# 03_USB_TO_UART.net
KiCad netlist of a schematic drawn in Altium Designer
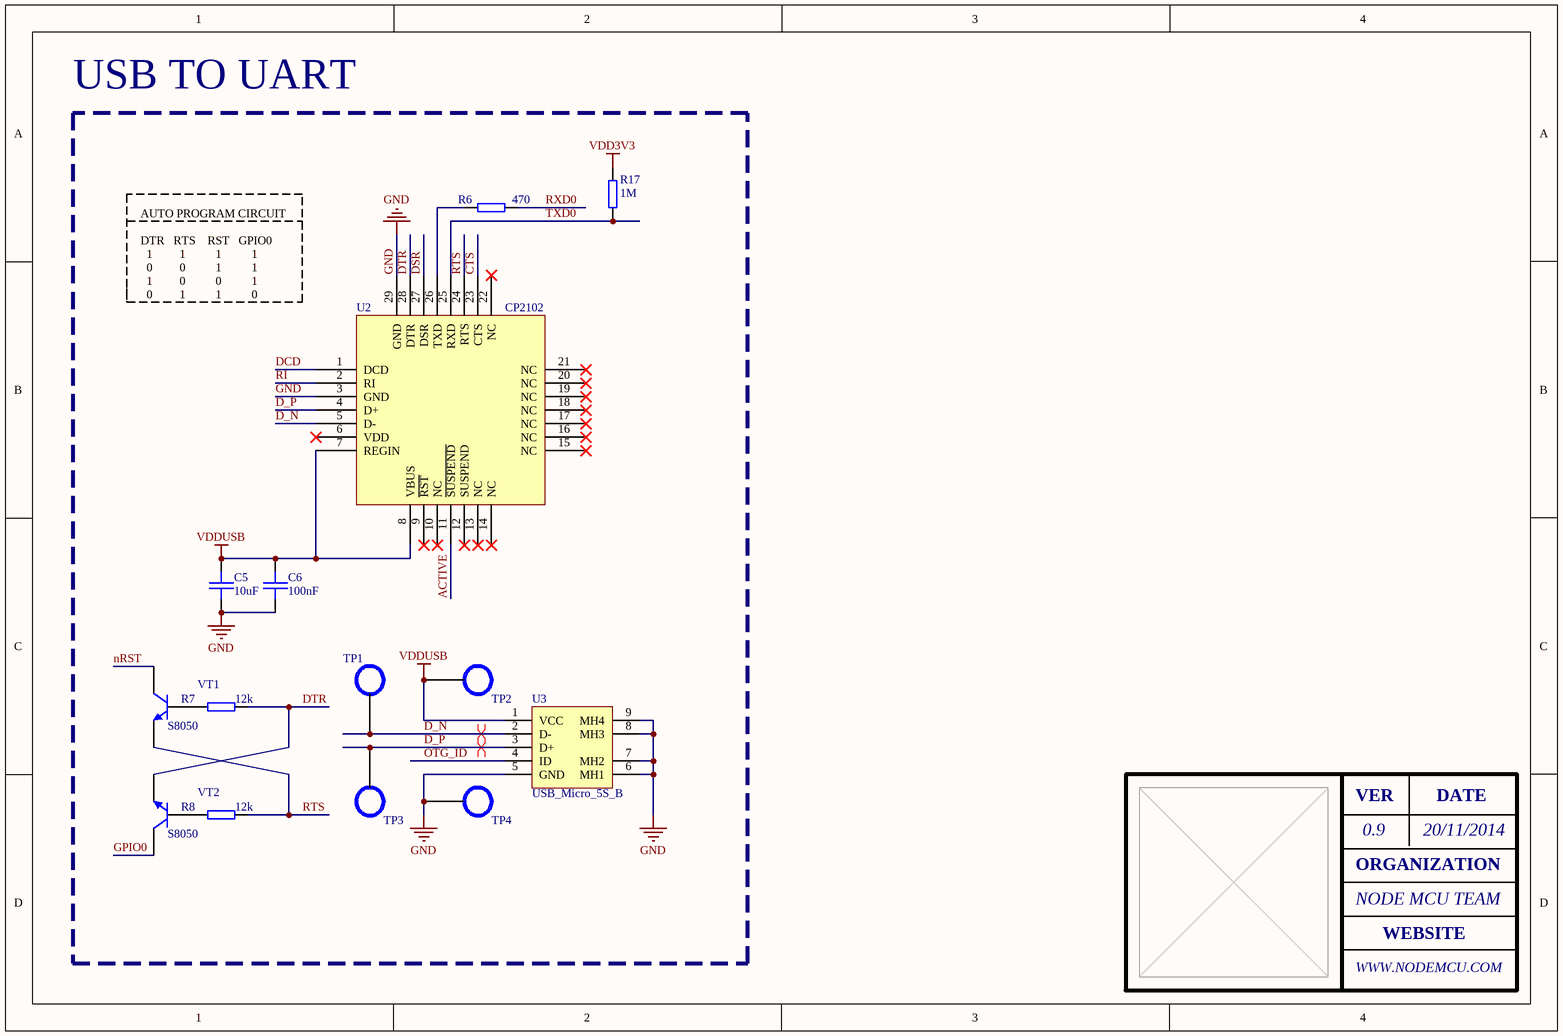
[diagram p0: 03_USB_TO_UART.SchDoc]

(export (version "E")
  (design (tool "Eeschema 10.0.6"))
  (components
    (comp (ref "C5")
      (value "10uF")
      (footprint "SMT_C_0402")
      (description "Surface mount capacitor 0402")
      (libsource (lib "Vowstar_Basic_Device") (part "SMT_C_0402"))
    )
    (comp (ref "C6")
      (value "100nF")
      (footprint "SMT_C_0402")
      (description "Surface mount capacitor 0402")
      (libsource (lib "Vowstar_Basic_Device") (part "SMT_C_0402"))
    )
    (comp (ref "R6")
      (value "470")
      (footprint "SMT_R_0402")
      (description "Surface mount resistor 0402")
      (libsource (lib "Vowstar_Basic_Device") (part "SMT_R_0402"))
    )
    (comp (ref "R7")
      (value "12k")
      (footprint "SMT_R_0402")
      (description "Surface mount resistor 0402")
      (libsource (lib "Vowstar_Basic_Device") (part "SMT_R_0402"))
    )
    (comp (ref "R8")
      (value "12k")
      (footprint "SMT_R_0402")
      (description "Surface mount resistor 0402")
      (libsource (lib "Vowstar_Basic_Device") (part "SMT_R_0402"))
    )
    (comp (ref "R17")
      (value "1M")
      (footprint "SMT_R_0402")
      (description "Surface mount resistor 0402")
      (libsource (lib "Vowstar_Basic_Device") (part "SMT_R_0402"))
    )
    (comp (ref "TP1")
      (value "TEST_POINT")
      (footprint "TEST_POINT")
      (description "Test point")
      (libsource (lib "koruza-compute-module-board") (part "TEST_POINT"))
    )
    (comp (ref "TP2")
      (value "TEST_POINT")
      (footprint "TEST_POINT")
      (description "Test point")
      (libsource (lib "koruza-compute-module-board") (part "TEST_POINT"))
    )
    (comp (ref "TP3")
      (value "TEST_POINT")
      (footprint "TEST_POINT")
      (description "Test point")
      (libsource (lib "koruza-compute-module-board") (part "TEST_POINT"))
    )
    (comp (ref "TP4")
      (value "TEST_POINT")
      (footprint "TEST_POINT")
      (description "Test point")
      (libsource (lib "koruza-compute-module-board") (part "TEST_POINT"))
    )
    (comp (ref "U2")
      (value "CP2102")
      (footprint "CP2102")
      (libsource (lib "Vowstar_IC_General") (part "CP2102"))
    )
    (comp (ref "U3")
      (value "USB_Micro_5S_B")
      (footprint "USB_MICRO_5S_B")
      (description "USB micro female SMT with 4 fixed foot")
      (libsource (lib "Vowstar_Connector") (part "USB_Micro_5S_B"))
    )
    (comp (ref "VT1")
      (value "S8050")
      (footprint "SMT_TRIODE_NPN")
      (description "Surface mount NPN transistor, package SOT-23")
      (libsource (lib "Vowstar_Basic_Device") (part "SMT_TRIODE_NPN"))
    )
    (comp (ref "VT2")
      (value "S8050")
      (footprint "SMT_TRIODE_NPN")
      (description "Surface mount NPN transistor, package SOT-23")
      (libsource (lib "Vowstar_Basic_Device") (part "SMT_TRIODE_NPN"))
    )
  )
  (nets
    (net (code "1") (name "/ACTIVE") (class "Default")
      (node (ref "U2") (pin "11") (pinfunction "~{SUSPEND}_11") (pintype "passive"))
    )
    (net (code "2") (name "/CTS") (class "Default")
      (node (ref "U2") (pin "23") (pinfunction "CTS_23") (pintype "passive"))
    )
    (net (code "3") (name "/DCD") (class "Default")
      (node (ref "U2") (pin "1") (pinfunction "DCD_1") (pintype "passive"))
    )
    (net (code "4") (name "/DSR") (class "Default")
      (node (ref "U2") (pin "27") (pinfunction "DSR_27") (pintype "passive"))
    )
    (net (code "5") (name "/DTR") (class "Default")
      (node (ref "R7") (pin "2") (pinfunction "2_2") (pintype "passive"))
      (node (ref "U2") (pin "28") (pinfunction "DTR_28") (pintype "passive"))
      (node (ref "VT2") (pin "2") (pinfunction "E_2") (pintype "passive"))
    )
    (net (code "6") (name "/D_N") (class "Default")
      (node (ref "TP1") (pin "1") (pinfunction "TP_1") (pintype "open_collector"))
      (node (ref "U2") (pin "5") (pinfunction "D-_5") (pintype "passive"))
      (node (ref "U3") (pin "2") (pinfunction "D-_2") (pintype "passive"))
    )
    (net (code "7") (name "/D_P") (class "Default")
      (node (ref "TP3") (pin "1") (pinfunction "TP_1") (pintype "open_collector"))
      (node (ref "U2") (pin "4") (pinfunction "D+_4") (pintype "passive"))
      (node (ref "U3") (pin "3") (pinfunction "D+_3") (pintype "passive"))
    )
    (net (code "8") (name "/GPIO0") (class "Default")
      (node (ref "VT2") (pin "3") (pinfunction "C_3") (pintype "passive"))
    )
    (net (code "9") (name "/OTG_ID") (class "Default")
      (node (ref "U3") (pin "4") (pinfunction "ID_4") (pintype "passive"))
    )
    (net (code "10") (name "/RI") (class "Default")
      (node (ref "U2") (pin "2") (pinfunction "RI_2") (pintype "passive"))
    )
    (net (code "11") (name "/RTS") (class "Default")
      (node (ref "R8") (pin "2") (pinfunction "2_2") (pintype "passive"))
      (node (ref "U2") (pin "24") (pinfunction "RTS_24") (pintype "passive"))
      (node (ref "VT1") (pin "2") (pinfunction "E_2") (pintype "passive"))
    )
    (net (code "12") (name "/RXD0") (class "Default")
      (node (ref "R6") (pin "2") (pinfunction "2_2") (pintype "passive"))
    )
    (net (code "13") (name "/TXD0") (class "Default")
      (node (ref "R17") (pin "1") (pinfunction "1_1") (pintype "passive"))
      (node (ref "U2") (pin "25") (pinfunction "RXD_25") (pintype "passive"))
    )
    (net (code "14") (name "/nRST") (class "Default")
      (node (ref "VT1") (pin "3") (pinfunction "C_3") (pintype "passive"))
    )
    (net (code "15") (name "GND") (class "Default")
      (node (ref "C5") (pin "2") (pinfunction "2_2") (pintype "passive"))
      (node (ref "C6") (pin "2") (pinfunction "2_2") (pintype "passive"))
      (node (ref "TP4") (pin "1") (pinfunction "TP_1") (pintype "open_collector"))
      (node (ref "U2") (pin "29") (pinfunction "GND_29") (pintype "passive"))
      (node (ref "U2") (pin "3") (pinfunction "GND_3") (pintype "passive"))
      (node (ref "U3") (pin "5") (pinfunction "GND_5") (pintype "passive"))
      (node (ref "U3") (pin "6") (pinfunction "MH1_6") (pintype "passive"))
      (node (ref "U3") (pin "7") (pinfunction "MH2_7") (pintype "passive"))
      (node (ref "U3") (pin "8") (pinfunction "MH3_8") (pintype "passive"))
      (node (ref "U3") (pin "9") (pinfunction "MH4_9") (pintype "passive"))
    )
    (net (code "16") (name "Net-(U2-TXD)") (class "Default")
      (node (ref "R6") (pin "1") (pinfunction "1_1") (pintype "passive"))
      (node (ref "U2") (pin "26") (pinfunction "TXD_26") (pintype "passive"))
    )
    (net (code "17") (name "Net-(VT1-B)") (class "Default")
      (node (ref "R7") (pin "1") (pinfunction "1_1") (pintype "passive"))
      (node (ref "VT1") (pin "1") (pinfunction "B_1") (pintype "passive"))
    )
    (net (code "18") (name "Net-(VT2-B)") (class "Default")
      (node (ref "R8") (pin "1") (pinfunction "1_1") (pintype "passive"))
      (node (ref "VT2") (pin "1") (pinfunction "B_1") (pintype "passive"))
    )
    (net (code "19") (name "VDD3V3") (class "Default")
      (node (ref "R17") (pin "2") (pinfunction "2_2") (pintype "passive"))
    )
    (net (code "20") (name "VDDUSB") (class "Default")
      (node (ref "C5") (pin "1") (pinfunction "1_1") (pintype "passive"))
      (node (ref "C6") (pin "1") (pinfunction "1_1") (pintype "passive"))
      (node (ref "TP2") (pin "1") (pinfunction "TP_1") (pintype "open_collector"))
      (node (ref "U2") (pin "7") (pinfunction "REGIN_7") (pintype "passive"))
      (node (ref "U2") (pin "8") (pinfunction "VBUS_8") (pintype "passive"))
      (node (ref "U3") (pin "1") (pinfunction "VCC_1") (pintype "passive"))
    )
    (net (code "21") (name "unconnected-(U2-NC-Pad10)") (class "Default")
      (node (ref "U2") (pin "10") (pinfunction "NC_10") (pintype "passive+no_connect"))
    )
    (net (code "22") (name "unconnected-(U2-NC-Pad13)") (class "Default")
      (node (ref "U2") (pin "13") (pinfunction "NC_13") (pintype "passive+no_connect"))
    )
    (net (code "23") (name "unconnected-(U2-NC-Pad14)") (class "Default")
      (node (ref "U2") (pin "14") (pinfunction "NC_14") (pintype "passive+no_connect"))
    )
    (net (code "24") (name "unconnected-(U2-NC-Pad15)") (class "Default")
      (node (ref "U2") (pin "15") (pinfunction "NC_15") (pintype "passive+no_connect"))
    )
    (net (code "25") (name "unconnected-(U2-NC-Pad16)") (class "Default")
      (node (ref "U2") (pin "16") (pinfunction "NC_16") (pintype "passive+no_connect"))
    )
    (net (code "26") (name "unconnected-(U2-NC-Pad17)") (class "Default")
      (node (ref "U2") (pin "17") (pinfunction "NC_17") (pintype "passive+no_connect"))
    )
    (net (code "27") (name "unconnected-(U2-NC-Pad18)") (class "Default")
      (node (ref "U2") (pin "18") (pinfunction "NC_18") (pintype "passive+no_connect"))
    )
    (net (code "28") (name "unconnected-(U2-NC-Pad19)") (class "Default")
      (node (ref "U2") (pin "19") (pinfunction "NC_19") (pintype "passive+no_connect"))
    )
    (net (code "29") (name "unconnected-(U2-NC-Pad20)") (class "Default")
      (node (ref "U2") (pin "20") (pinfunction "NC_20") (pintype "passive+no_connect"))
    )
    (net (code "30") (name "unconnected-(U2-NC-Pad21)") (class "Default")
      (node (ref "U2") (pin "21") (pinfunction "NC_21") (pintype "passive+no_connect"))
    )
    (net (code "31") (name "unconnected-(U2-NC-Pad22)") (class "Default")
      (node (ref "U2") (pin "22") (pinfunction "NC_22") (pintype "passive+no_connect"))
    )
    (net (code "32") (name "unconnected-(U2-SUSPEND-Pad12)") (class "Default")
      (node (ref "U2") (pin "12") (pinfunction "SUSPEND_12") (pintype "passive+no_connect"))
    )
    (net (code "33") (name "unconnected-(U2-VDD-Pad6)") (class "Default")
      (node (ref "U2") (pin "6") (pinfunction "VDD_6") (pintype "passive+no_connect"))
    )
    (net (code "34") (name "unconnected-(U2-~{RST}-Pad9)") (class "Default")
      (node (ref "U2") (pin "9") (pinfunction "~{RST}_9") (pintype "passive+no_connect"))
    )
  )
)
